# d700_decoder.net
KiCad netlist of a schematic drawn in EAGLE
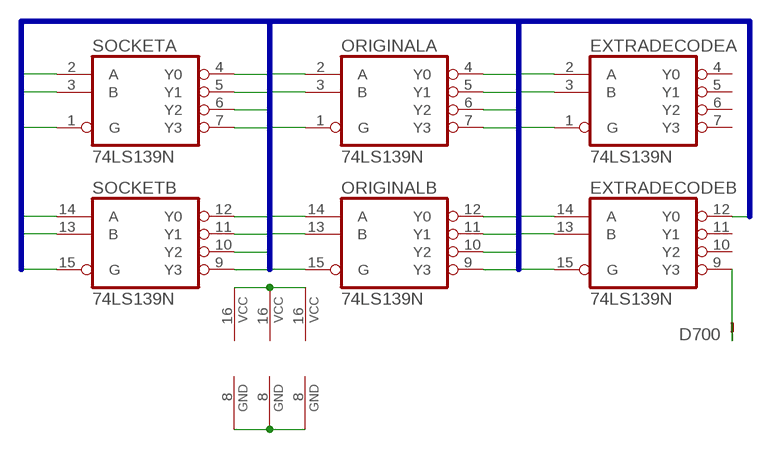
[diagram p0: schematic, sheet 1]

(export (version "E")
  (design (tool "Eeschema 10.0.6"))
  (components
    (comp (ref "D700")
      (value "TP")
      (footprint "eagle-import:JP1")
      (libsource (lib "eagle-import") (part "TP"))
    )
    (comp (ref "EXTRADECODE")
      (value "74LS139N")
      (footprint "eagle-import:DIL16")
      (libsource (lib "eagle-import") (part "74139NLS"))
    )
    (comp (ref "ORIGINAL")
      (value "74LS139N")
      (footprint "eagle-import:DIL16")
      (libsource (lib "eagle-import") (part "74139NLS"))
    )
    (comp (ref "SOCKET")
      (value "74LS139N")
      (footprint "eagle-import:DIL16")
      (libsource (lib "eagle-import") (part "74139NLS"))
    )
  )
  (nets
    (net (code "1") (name "/A(2)") (class "Default")
      (node (ref "EXTRADECODE") (pin "2") (pinfunction "A_2") (pintype "input"))
      (node (ref "ORIGINAL") (pin "2") (pinfunction "A_2") (pintype "input"))
      (node (ref "SOCKET") (pin "2") (pinfunction "A_2") (pintype "input"))
    )
    (net (code "2") (name "/A(14)") (class "Default")
      (node (ref "EXTRADECODE") (pin "14") (pinfunction "A_14") (pintype "input"))
      (node (ref "ORIGINAL") (pin "14") (pinfunction "A_14") (pintype "input"))
      (node (ref "SOCKET") (pin "14") (pinfunction "A_14") (pintype "input"))
    )
    (net (code "3") (name "/B(3)") (class "Default")
      (node (ref "EXTRADECODE") (pin "3") (pinfunction "B_3") (pintype "input"))
      (node (ref "ORIGINAL") (pin "3") (pinfunction "B_3") (pintype "input"))
      (node (ref "SOCKET") (pin "3") (pinfunction "B_3") (pintype "input"))
    )
    (net (code "4") (name "/B(13)") (class "Default")
      (node (ref "EXTRADECODE") (pin "13") (pinfunction "B_13") (pintype "input"))
      (node (ref "ORIGINAL") (pin "13") (pinfunction "B_13") (pintype "input"))
      (node (ref "SOCKET") (pin "13") (pinfunction "B_13") (pintype "input"))
    )
    (net (code "5") (name "/G(1)") (class "Default")
      (node (ref "EXTRADECODE") (pin "1") (pinfunction "G_1") (pintype "input"))
      (node (ref "ORIGINAL") (pin "1") (pinfunction "G_1") (pintype "input"))
      (node (ref "SOCKET") (pin "1") (pinfunction "G_1") (pintype "input"))
    )
    (net (code "6") (name "/G(15)") (class "Default")
      (node (ref "ORIGINAL") (pin "15") (pinfunction "G_15") (pintype "input"))
      (node (ref "SOCKET") (pin "15") (pinfunction "G_15") (pintype "input"))
    )
    (net (code "7") (name "/SIDINTERNAL") (class "Default")
      (node (ref "EXTRADECODE") (pin "15") (pinfunction "G_15") (pintype "input"))
      (node (ref "ORIGINAL") (pin "5") (pinfunction "Y1_5") (pintype "output"))
    )
    (net (code "8") (name "/Y0(4-VICOUT)") (class "Default")
      (node (ref "ORIGINAL") (pin "4") (pinfunction "Y0_4") (pintype "output"))
      (node (ref "SOCKET") (pin "4") (pinfunction "Y0_4") (pintype "output"))
    )
    (net (code "9") (name "/Y0(12)") (class "Default")
      (node (ref "ORIGINAL") (pin "12") (pinfunction "Y0_12") (pintype "output"))
      (node (ref "SOCKET") (pin "12") (pinfunction "Y0_12") (pintype "output"))
    )
    (net (code "10") (name "/Y1(5-SIDOUT)") (class "Default")
      (node (ref "EXTRADECODE") (pin "12") (pinfunction "Y0_12") (pintype "output"))
      (node (ref "SOCKET") (pin "5") (pinfunction "Y1_5") (pintype "output"))
    )
    (net (code "11") (name "/Y1(11)") (class "Default")
      (node (ref "ORIGINAL") (pin "11") (pinfunction "Y1_11") (pintype "output"))
      (node (ref "SOCKET") (pin "11") (pinfunction "Y1_11") (pintype "output"))
    )
    (net (code "12") (name "/Y2(6)") (class "Default")
      (node (ref "ORIGINAL") (pin "6") (pinfunction "Y2_6") (pintype "output"))
      (node (ref "SOCKET") (pin "6") (pinfunction "Y2_6") (pintype "output"))
    )
    (net (code "13") (name "/Y2(10)") (class "Default")
      (node (ref "ORIGINAL") (pin "10") (pinfunction "Y2_10") (pintype "output"))
      (node (ref "SOCKET") (pin "10") (pinfunction "Y2_10") (pintype "output"))
    )
    (net (code "14") (name "/Y3(7)") (class "Default")
      (node (ref "ORIGINAL") (pin "7") (pinfunction "Y3_7") (pintype "output"))
      (node (ref "SOCKET") (pin "7") (pinfunction "Y3_7") (pintype "output"))
    )
    (net (code "15") (name "/Y3(9)") (class "Default")
      (node (ref "ORIGINAL") (pin "9") (pinfunction "Y3_9") (pintype "output"))
      (node (ref "SOCKET") (pin "9") (pinfunction "Y3_9") (pintype "output"))
    )
    (net (code "16") (name "Net-(EXTRADECODEB-Y3)") (class "Default")
      (node (ref "D700") (pin "1") (pinfunction "1_1") (pintype "passive"))
      (node (ref "EXTRADECODE") (pin "9") (pinfunction "Y3_9") (pintype "output"))
    )
    (net (code "17") (name "Net-(EXTRADECODEC-GND)") (class "Default")
      (node (ref "EXTRADECODE") (pin "8") (pinfunction "GND_8") (pintype "power_in"))
      (node (ref "ORIGINAL") (pin "8") (pinfunction "GND_8") (pintype "power_in"))
      (node (ref "SOCKET") (pin "8") (pinfunction "GND_8") (pintype "power_in"))
    )
    (net (code "18") (name "Net-(EXTRADECODEC-VCC)") (class "Default")
      (node (ref "EXTRADECODE") (pin "16") (pinfunction "VCC_16") (pintype "power_in"))
      (node (ref "ORIGINAL") (pin "16") (pinfunction "VCC_16") (pintype "power_in"))
      (node (ref "SOCKET") (pin "16") (pinfunction "VCC_16") (pintype "power_in"))
    )
    (net (code "19") (name "unconnected-(EXTRADECODEA-Y0-Pad4)") (class "Default")
      (node (ref "EXTRADECODE") (pin "4") (pinfunction "Y0_4") (pintype "output"))
    )
    (net (code "20") (name "unconnected-(EXTRADECODEA-Y1-Pad5)") (class "Default")
      (node (ref "EXTRADECODE") (pin "5") (pinfunction "Y1_5") (pintype "output"))
    )
    (net (code "21") (name "unconnected-(EXTRADECODEA-Y2-Pad6)") (class "Default")
      (node (ref "EXTRADECODE") (pin "6") (pinfunction "Y2_6") (pintype "output"))
    )
    (net (code "22") (name "unconnected-(EXTRADECODEA-Y3-Pad7)") (class "Default")
      (node (ref "EXTRADECODE") (pin "7") (pinfunction "Y3_7") (pintype "output"))
    )
    (net (code "23") (name "unconnected-(EXTRADECODEB-Y1-Pad11)") (class "Default")
      (node (ref "EXTRADECODE") (pin "11") (pinfunction "Y1_11") (pintype "output"))
    )
    (net (code "24") (name "unconnected-(EXTRADECODEB-Y2-Pad10)") (class "Default")
      (node (ref "EXTRADECODE") (pin "10") (pinfunction "Y2_10") (pintype "output"))
    )
  )
)
